# Movimiento.net
KiCad netlist of a schematic drawn in EAGLE
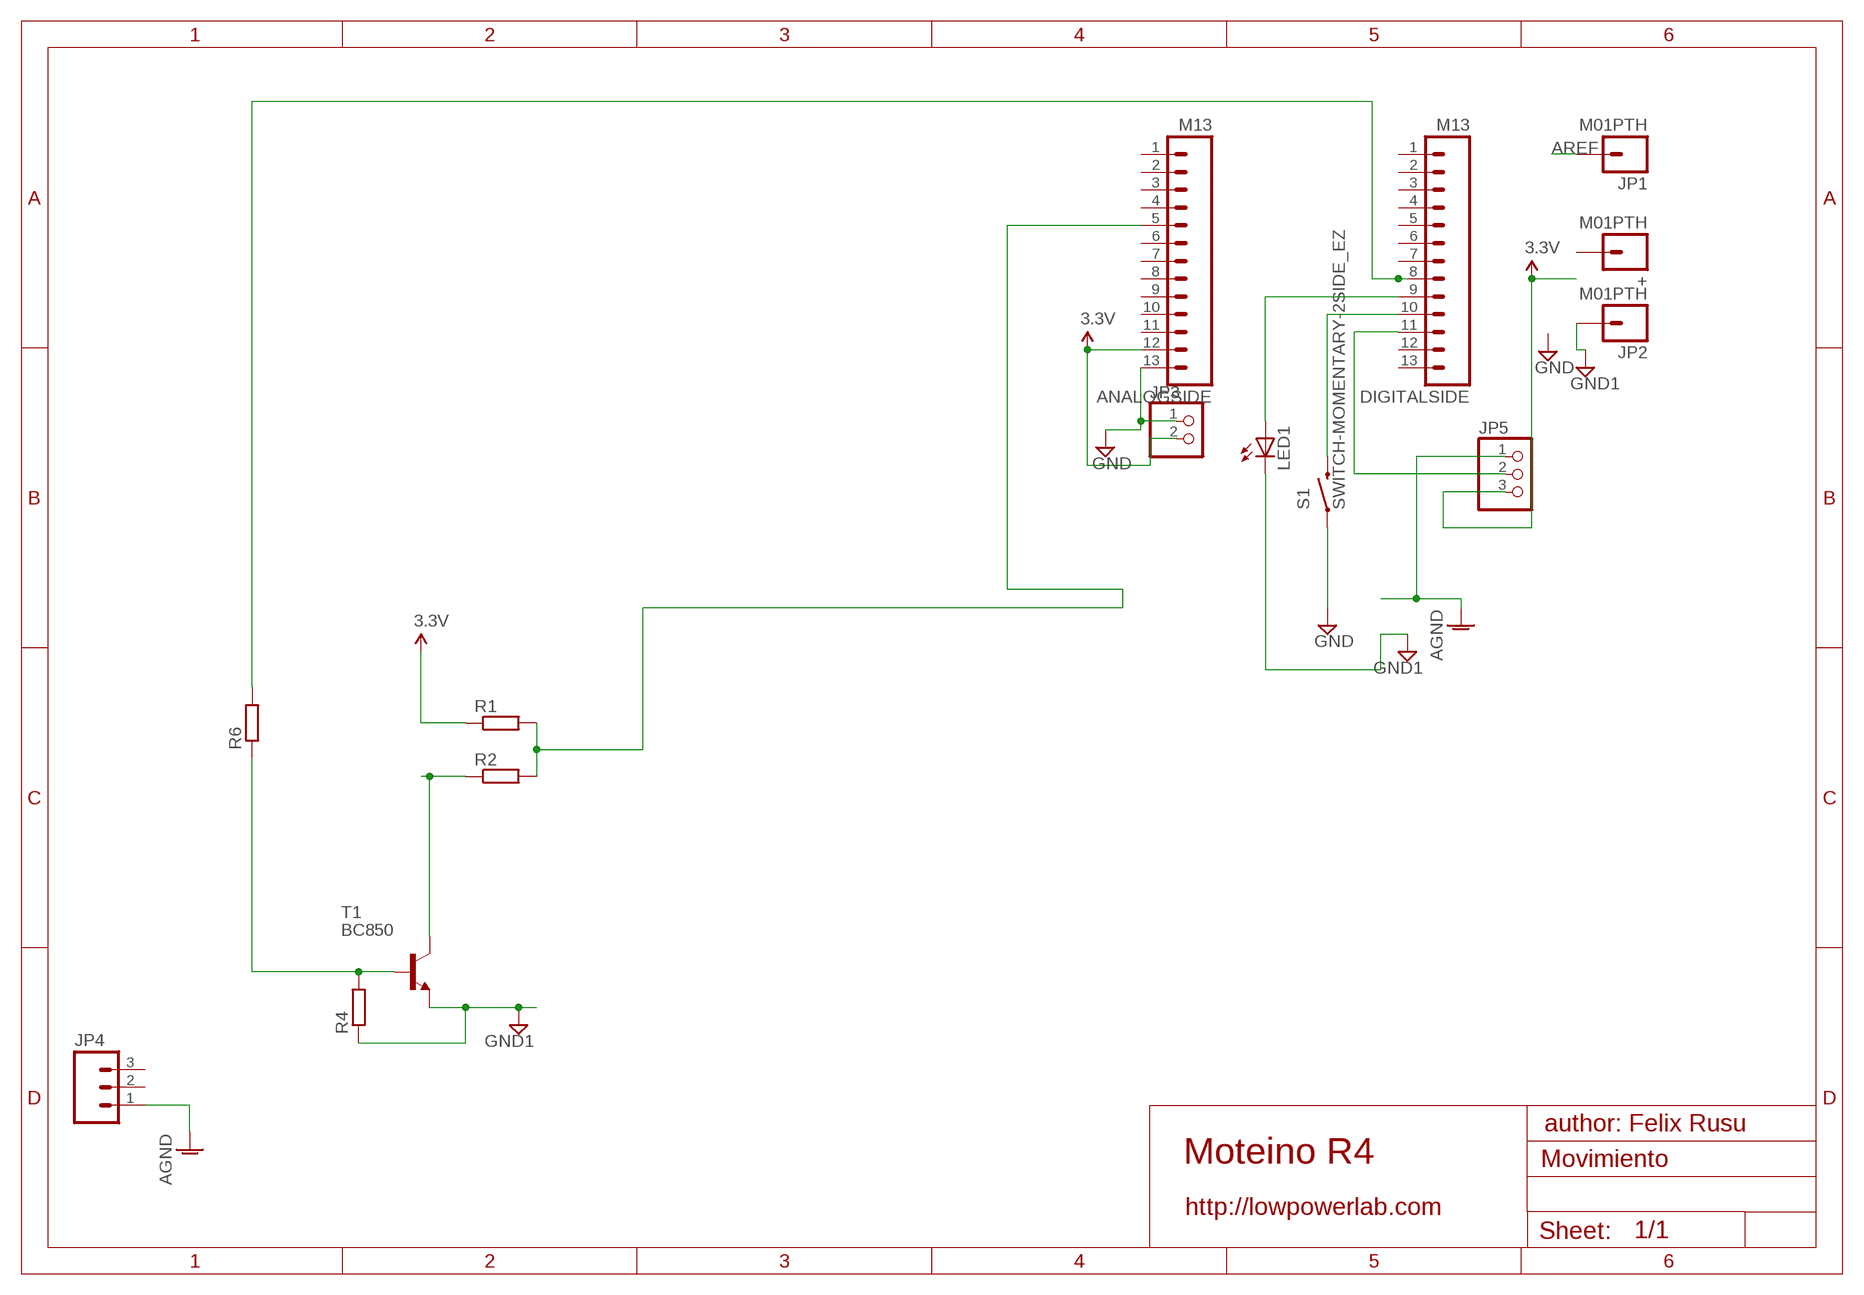
[diagram p0: schematic, sheet 1]

(export (version "E")
  (design (tool "Eeschema 10.0.6"))
  (components
    (comp (ref "+")
      (value "M01PTH")
      (footprint "eagle-import:1X01")
      (libsource (lib "eagle-import") (part "M01PTH"))
    )
    (comp (ref "ANALOGSIDE")
      (value "M13")
      (footprint "eagle-import:1X13")
      (libsource (lib "eagle-import") (part "M13"))
    )
    (comp (ref "DIGITALSIDE")
      (value "M13")
      (footprint "eagle-import:1X13")
      (libsource (lib "eagle-import") (part "M13"))
    )
    (comp (ref "JP1")
      (value "M01PTH")
      (footprint "eagle-import:1X01")
      (libsource (lib "eagle-import") (part "M01PTH"))
    )
    (comp (ref "JP2")
      (value "M01PTH")
      (footprint "eagle-import:1X01")
      (libsource (lib "eagle-import") (part "M01PTH"))
    )
    (comp (ref "JP3")
      (value "PINHD-1X2")
      (footprint "eagle-import:1X02")
      (libsource (lib "eagle-import") (part "PINHD-1X2"))
    )
    (comp (ref "JP4")
      (value "M03PTH")
      (footprint "eagle-import:1X03")
      (libsource (lib "eagle-import") (part "M03PTH"))
    )
    (comp (ref "JP5")
      (value "PINHD-1X3")
      (footprint "eagle-import:1X03")
      (libsource (lib "eagle-import") (part "PINHD-1X3"))
    )
    (comp (ref "LED1")
      (value "LED3MM")
      (footprint "eagle-import:LED3MM")
      (libsource (lib "eagle-import") (part "LED3MM"))
    )
    (comp (ref "R1")
      (value "R-EU_0204/7")
      (footprint "eagle-import:0204_7")
      (libsource (lib "eagle-import") (part "R-EU_0204/7"))
    )
    (comp (ref "R2")
      (value "R-EU_0204/7")
      (footprint "eagle-import:0204_7")
      (libsource (lib "eagle-import") (part "R-EU_0204/7"))
    )
    (comp (ref "R4")
      (value "R-EU_M1206")
      (footprint "eagle-import:M1206")
      (libsource (lib "eagle-import") (part "R-EU_M1206"))
    )
    (comp (ref "R6")
      (value "R-EU_M1206")
      (footprint "eagle-import:M1206")
      (libsource (lib "eagle-import") (part "R-EU_M1206"))
    )
    (comp (ref "S1")
      (value "SWITCH-MOMENTARY-2SIDE_EZ")
      (footprint "eagle-import:TACTILE-PTH-SIDEEZ")
      (libsource (lib "eagle-import") (part "SWITCH-MOMENTARY-2SIDE_EZ"))
    )
    (comp (ref "T1")
      (value "BC850")
      (footprint "eagle-import:SOT23")
      (libsource (lib "eagle-import") (part "BC850"))
    )
  )
  (nets
    (net (code "1") (name "/AREF") (class "Default")
      (node (ref "JP1") (pin "1") (pinfunction "1_1") (pintype "passive"))
    )
    (net (code "2") (name "3.3V") (class "Default")
      (node (ref "ANALOGSIDE") (pin "12") (pinfunction "12_12") (pintype "passive"))
      (node (ref "JP3") (pin "2") (pinfunction "2_2") (pintype "passive"))
      (node (ref "JP5") (pin "3") (pinfunction "3_3") (pintype "passive"))
      (node (ref "R1") (pin "1") (pinfunction "1_1") (pintype "passive"))
    )
    (net (code "3") (name "AGND") (class "Default")
      (node (ref "JP4") (pin "1") (pinfunction "1_1") (pintype "passive"))
      (node (ref "JP5") (pin "1") (pinfunction "1_1") (pintype "passive"))
    )
    (net (code "4") (name "GND") (class "Default")
      (node (ref "ANALOGSIDE") (pin "13") (pinfunction "13_13") (pintype "passive"))
      (node (ref "JP3") (pin "1") (pinfunction "1_1") (pintype "passive"))
      (node (ref "S1") (pin "1") (pinfunction "1_1") (pintype "passive"))
    )
    (net (code "5") (name "GND1") (class "Default")
      (node (ref "JP2") (pin "1") (pinfunction "1_1") (pintype "passive"))
      (node (ref "LED1") (pin "K") (pinfunction "C_K") (pintype "passive"))
      (node (ref "R4") (pin "1") (pinfunction "1_1") (pintype "passive"))
      (node (ref "T1") (pin "2") (pinfunction "E_2") (pintype "passive"))
    )
    (net (code "6") (name "Net-(ANALOGSIDE-Pad5)") (class "Default")
      (node (ref "ANALOGSIDE") (pin "5") (pinfunction "5_5") (pintype "passive"))
      (node (ref "R1") (pin "2") (pinfunction "2_2") (pintype "passive"))
      (node (ref "R2") (pin "2") (pinfunction "2_2") (pintype "passive"))
    )
    (net (code "7") (name "Net-(DIGITALSIDE-Pad8)") (class "Default")
      (node (ref "DIGITALSIDE") (pin "8") (pinfunction "8_8") (pintype "passive"))
      (node (ref "R6") (pin "2") (pinfunction "2_2") (pintype "passive"))
    )
    (net (code "8") (name "Net-(DIGITALSIDE-Pad9)") (class "Default")
      (node (ref "DIGITALSIDE") (pin "9") (pinfunction "9_9") (pintype "passive"))
      (node (ref "LED1") (pin "A") (pinfunction "A_A") (pintype "passive"))
    )
    (net (code "9") (name "Net-(DIGITALSIDE-Pad10)") (class "Default")
      (node (ref "DIGITALSIDE") (pin "10") (pinfunction "10_10") (pintype "passive"))
      (node (ref "S1") (pin "2") (pinfunction "2_2") (pintype "passive"))
    )
    (net (code "10") (name "Net-(DIGITALSIDE-Pad11)") (class "Default")
      (node (ref "DIGITALSIDE") (pin "11") (pinfunction "11_11") (pintype "passive"))
      (node (ref "JP5") (pin "2") (pinfunction "2_2") (pintype "passive"))
    )
    (net (code "11") (name "Net-(T1-B)") (class "Default")
      (node (ref "R4") (pin "2") (pinfunction "2_2") (pintype "passive"))
      (node (ref "R6") (pin "1") (pinfunction "1_1") (pintype "passive"))
      (node (ref "T1") (pin "1") (pinfunction "B_1") (pintype "passive"))
    )
    (net (code "12") (name "Net-(T1-C)") (class "Default")
      (node (ref "R2") (pin "1") (pinfunction "1_1") (pintype "passive"))
      (node (ref "T1") (pin "3") (pinfunction "C_3") (pintype "passive"))
    )
    (net (code "13") (name "unconnected-(+-Pad1)") (class "Default")
      (node (ref "+") (pin "1") (pinfunction "1_1") (pintype "passive"))
    )
    (net (code "14") (name "unconnected-(ANALOGSIDE-Pad1)") (class "Default")
      (node (ref "ANALOGSIDE") (pin "1") (pinfunction "1_1") (pintype "passive"))
    )
    (net (code "15") (name "unconnected-(ANALOGSIDE-Pad2)") (class "Default")
      (node (ref "ANALOGSIDE") (pin "2") (pinfunction "2_2") (pintype "passive"))
    )
    (net (code "16") (name "unconnected-(ANALOGSIDE-Pad3)") (class "Default")
      (node (ref "ANALOGSIDE") (pin "3") (pinfunction "3_3") (pintype "passive"))
    )
    (net (code "17") (name "unconnected-(ANALOGSIDE-Pad4)") (class "Default")
      (node (ref "ANALOGSIDE") (pin "4") (pinfunction "4_4") (pintype "passive"))
    )
    (net (code "18") (name "unconnected-(ANALOGSIDE-Pad6)") (class "Default")
      (node (ref "ANALOGSIDE") (pin "6") (pinfunction "6_6") (pintype "passive"))
    )
    (net (code "19") (name "unconnected-(ANALOGSIDE-Pad7)") (class "Default")
      (node (ref "ANALOGSIDE") (pin "7") (pinfunction "7_7") (pintype "passive"))
    )
    (net (code "20") (name "unconnected-(ANALOGSIDE-Pad8)") (class "Default")
      (node (ref "ANALOGSIDE") (pin "8") (pinfunction "8_8") (pintype "passive"))
    )
    (net (code "21") (name "unconnected-(ANALOGSIDE-Pad9)") (class "Default")
      (node (ref "ANALOGSIDE") (pin "9") (pinfunction "9_9") (pintype "passive"))
    )
    (net (code "22") (name "unconnected-(ANALOGSIDE-Pad10)") (class "Default")
      (node (ref "ANALOGSIDE") (pin "10") (pinfunction "10_10") (pintype "passive"))
    )
    (net (code "23") (name "unconnected-(ANALOGSIDE-Pad11)") (class "Default")
      (node (ref "ANALOGSIDE") (pin "11") (pinfunction "11_11") (pintype "passive"))
    )
    (net (code "24") (name "unconnected-(DIGITALSIDE-Pad1)") (class "Default")
      (node (ref "DIGITALSIDE") (pin "1") (pinfunction "1_1") (pintype "passive"))
    )
    (net (code "25") (name "unconnected-(DIGITALSIDE-Pad2)") (class "Default")
      (node (ref "DIGITALSIDE") (pin "2") (pinfunction "2_2") (pintype "passive"))
    )
    (net (code "26") (name "unconnected-(DIGITALSIDE-Pad3)") (class "Default")
      (node (ref "DIGITALSIDE") (pin "3") (pinfunction "3_3") (pintype "passive"))
    )
    (net (code "27") (name "unconnected-(DIGITALSIDE-Pad4)") (class "Default")
      (node (ref "DIGITALSIDE") (pin "4") (pinfunction "4_4") (pintype "passive"))
    )
    (net (code "28") (name "unconnected-(DIGITALSIDE-Pad5)") (class "Default")
      (node (ref "DIGITALSIDE") (pin "5") (pinfunction "5_5") (pintype "passive"))
    )
    (net (code "29") (name "unconnected-(DIGITALSIDE-Pad6)") (class "Default")
      (node (ref "DIGITALSIDE") (pin "6") (pinfunction "6_6") (pintype "passive"))
    )
    (net (code "30") (name "unconnected-(DIGITALSIDE-Pad7)") (class "Default")
      (node (ref "DIGITALSIDE") (pin "7") (pinfunction "7_7") (pintype "passive"))
    )
    (net (code "31") (name "unconnected-(DIGITALSIDE-Pad12)") (class "Default")
      (node (ref "DIGITALSIDE") (pin "12") (pinfunction "12_12") (pintype "passive"))
    )
    (net (code "32") (name "unconnected-(DIGITALSIDE-Pad13)") (class "Default")
      (node (ref "DIGITALSIDE") (pin "13") (pinfunction "13_13") (pintype "passive"))
    )
    (net (code "33") (name "unconnected-(JP4-Pad2)") (class "Default")
      (node (ref "JP4") (pin "2") (pinfunction "2_2") (pintype "passive"))
    )
    (net (code "34") (name "unconnected-(JP4-Pad3)") (class "Default")
      (node (ref "JP4") (pin "3") (pinfunction "3_3") (pintype "passive"))
    )
  )
)
